# AY_Card_V2.net
KiCad netlist of a schematic drawn in EAGLE
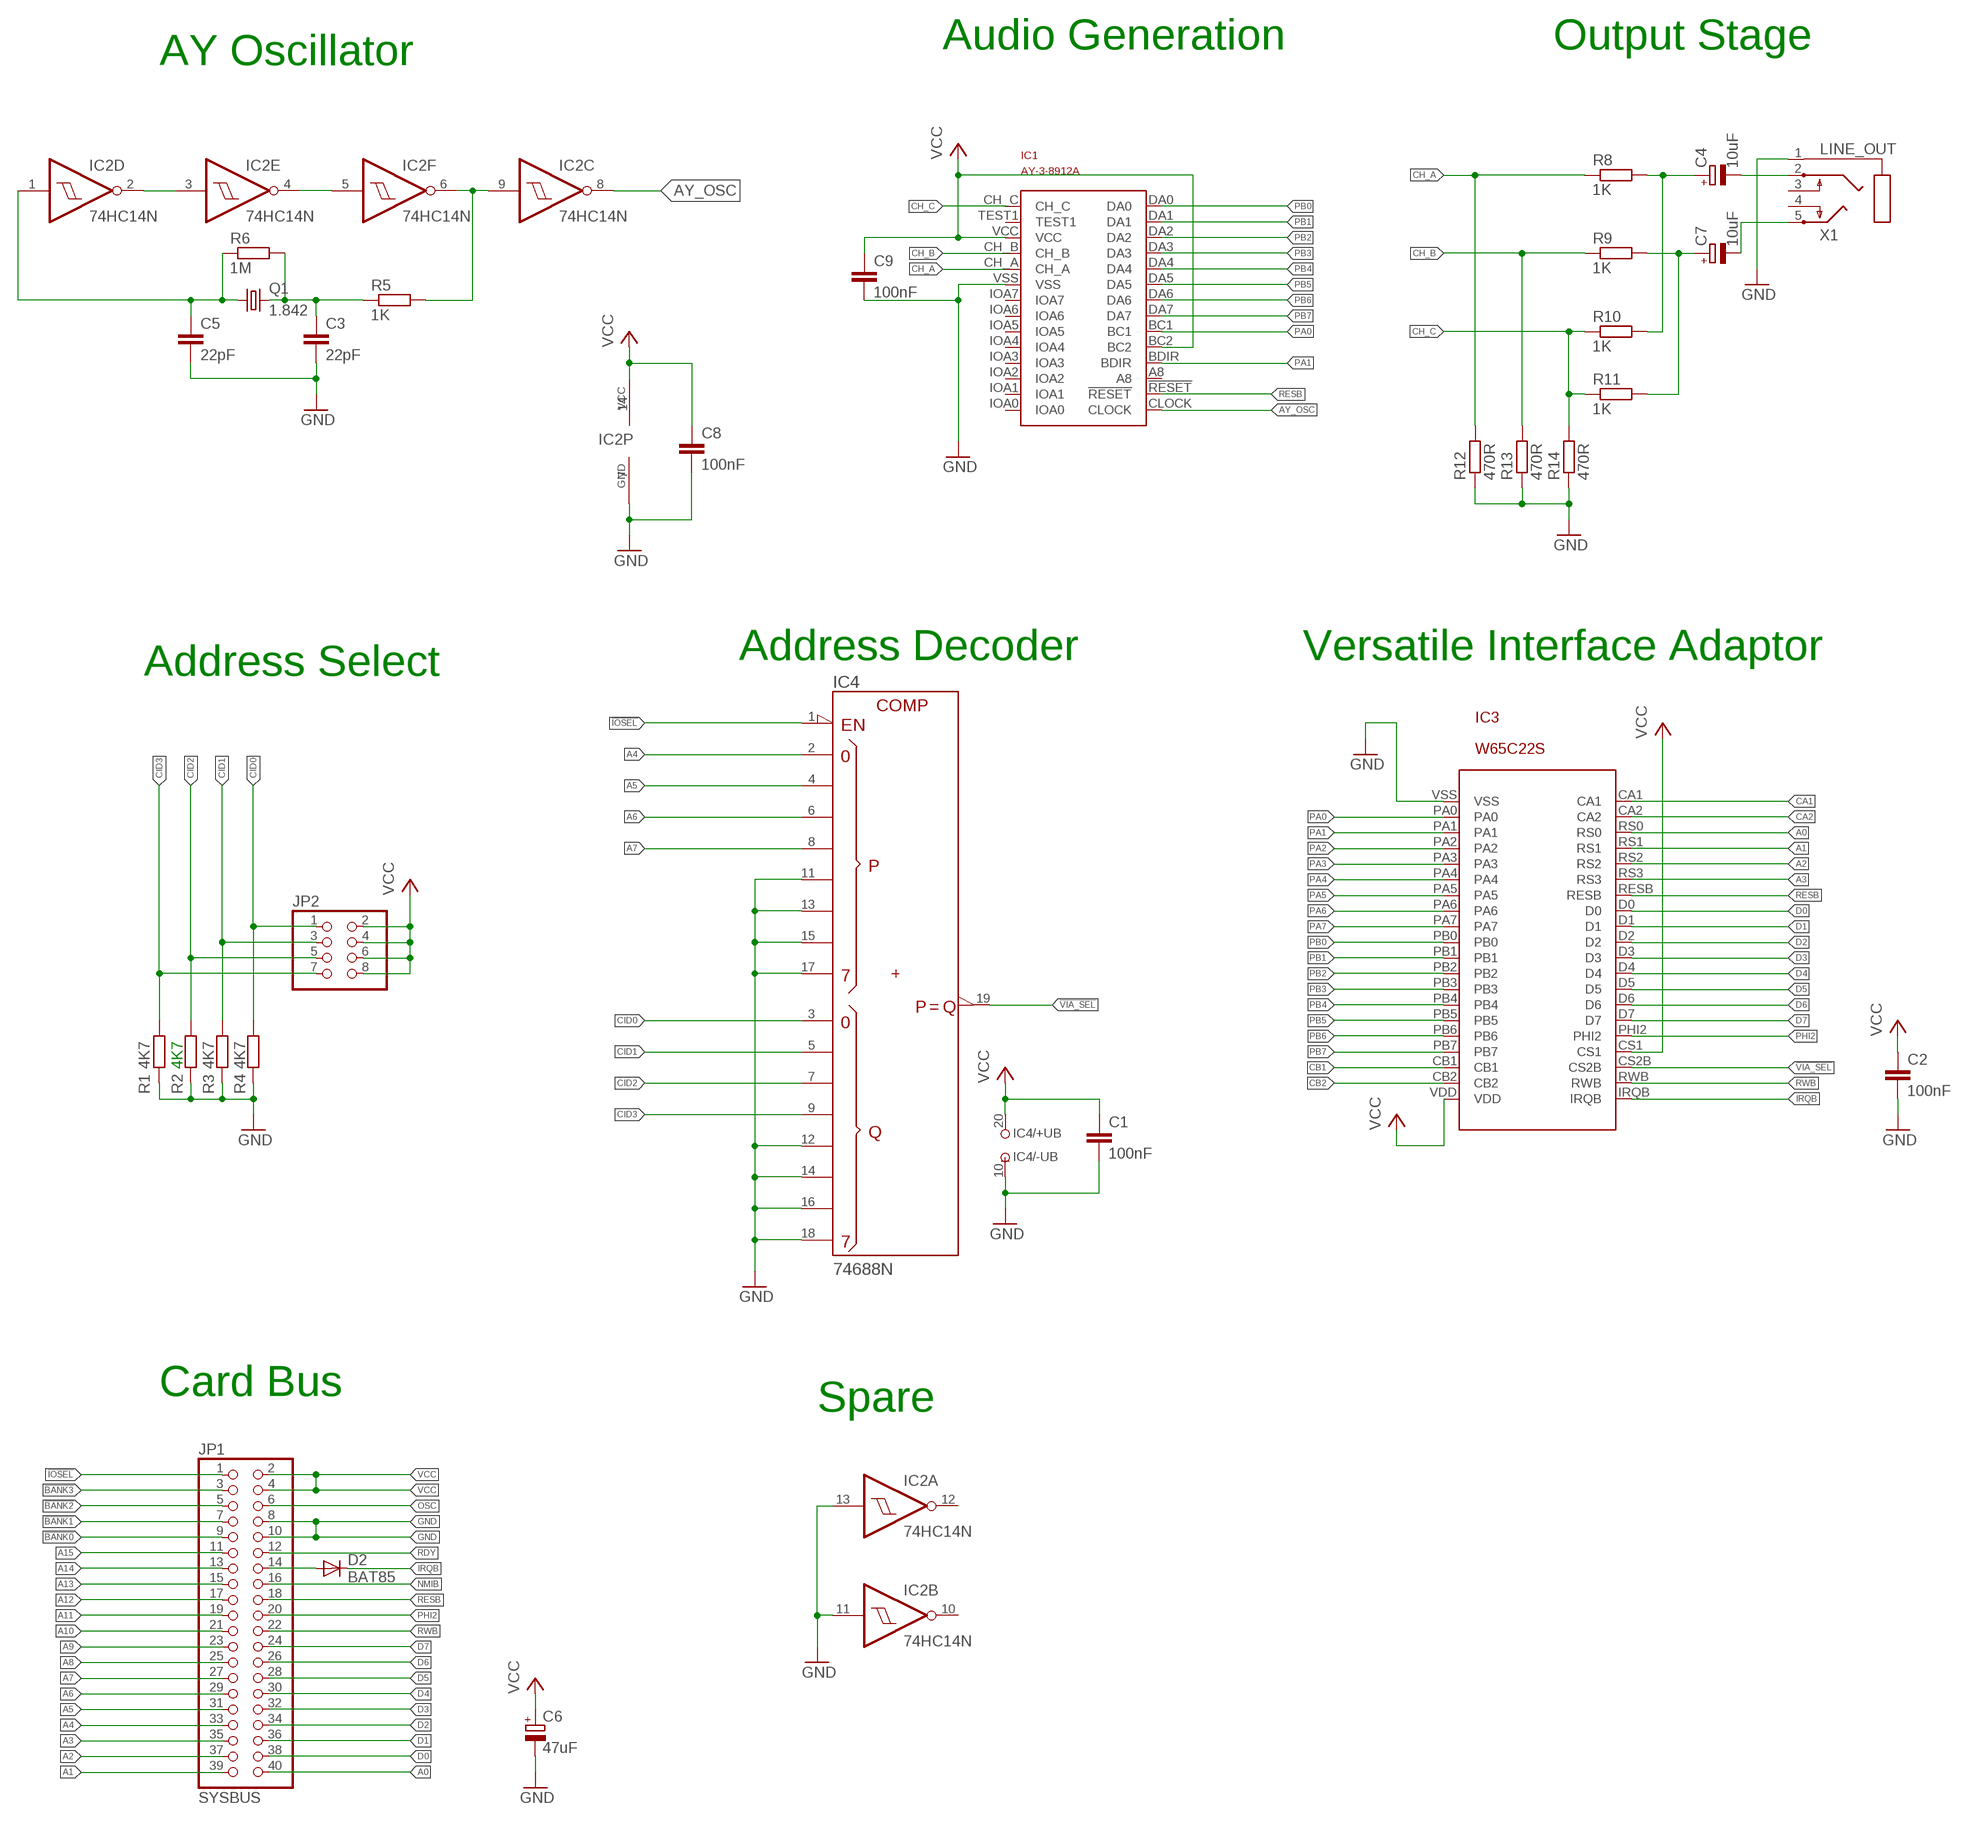
[diagram p0: schematic, sheet 1]

(export (version "E")
  (design (tool "Eeschema 10.0.6"))
  (components
    (comp (ref "C1")
      (value "100nF")
      (footprint "eagle-import:C050-025X075")
      (libsource (lib "eagle-import") (part "C-EU050-025X075"))
    )
    (comp (ref "C2")
      (value "100nF")
      (footprint "eagle-import:C050-025X075")
      (libsource (lib "eagle-import") (part "C-EU050-025X075"))
    )
    (comp (ref "C3")
      (value "22pF")
      (footprint "eagle-import:C050-025X075")
      (libsource (lib "eagle-import") (part "C-EU050-025X075"))
    )
    (comp (ref "C4")
      (value "10uF")
      (footprint "eagle-import:E2-5")
      (libsource (lib "eagle-import") (part "CPOL-EUE2-5"))
    )
    (comp (ref "C5")
      (value "22pF")
      (footprint "eagle-import:C050-025X075")
      (libsource (lib "eagle-import") (part "C-EU050-025X075"))
    )
    (comp (ref "C6")
      (value "47uF")
      (footprint "eagle-import:E2,5-7")
      (libsource (lib "eagle-import") (part "CPOL-EUE2.5-7"))
    )
    (comp (ref "C7")
      (value "10uF")
      (footprint "eagle-import:E2-5")
      (libsource (lib "eagle-import") (part "CPOL-EUE2-5"))
    )
    (comp (ref "C8")
      (value "100nF")
      (footprint "eagle-import:C050-025X075")
      (libsource (lib "eagle-import") (part "C-EU050-025X075"))
    )
    (comp (ref "C9")
      (value "100nF")
      (footprint "eagle-import:C050-025X075")
      (libsource (lib "eagle-import") (part "C-EU050-025X075"))
    )
    (comp (ref "D2")
      (value "BAT85")
      (footprint "eagle-import:DO34-7")
      (libsource (lib "eagle-import") (part "BAT81"))
    )
    (comp (ref "IC1")
      (value "AY-3-8912A")
      (footprint "eagle-import:DIP")
      (libsource (lib "eagle-import") (part "AY-3-8912-DIP"))
    )
    (comp (ref "IC2")
      (value "74HC14N")
      (footprint "eagle-import:DIL14")
      (libsource (lib "eagle-import") (part "7414N"))
    )
    (comp (ref "IC3")
      (value "W65C22S")
      (footprint "eagle-import:W65C22-DIP")
      (libsource (lib "eagle-import") (part "W65C22"))
    )
    (comp (ref "IC4")
      (value "74688N")
      (footprint "eagle-import:DIL20")
      (libsource (lib "eagle-import") (part "74688N"))
    )
    (comp (ref "JP1")
      (value "SYSBUS")
      (footprint "eagle-import:2X20_90")
      (libsource (lib "eagle-import") (part "PINHD-2X20/90"))
    )
    (comp (ref "JP2")
      (value "PINHD-2X4")
      (footprint "eagle-import:2X04")
      (libsource (lib "eagle-import") (part "PINHD-2X4"))
    )
    (comp (ref "Q1")
      (value "1.842")
      (footprint "eagle-import:HC49_S")
      (libsource (lib "eagle-import") (part "CRYSTALHC49S"))
    )
    (comp (ref "R1")
      (value "4K7")
      (footprint "eagle-import:0207_10")
      (libsource (lib "eagle-import") (part "R-EU_0207/10"))
    )
    (comp (ref "R2")
      (value "4K7")
      (footprint "eagle-import:0207_10")
      (libsource (lib "eagle-import") (part "R-EU_0207/10"))
    )
    (comp (ref "R3")
      (value "4K7")
      (footprint "eagle-import:0207_10")
      (libsource (lib "eagle-import") (part "R-EU_0207/10"))
    )
    (comp (ref "R4")
      (value "4K7")
      (footprint "eagle-import:0207_10")
      (libsource (lib "eagle-import") (part "R-EU_0207/10"))
    )
    (comp (ref "R5")
      (value "1K")
      (footprint "eagle-import:0207_2V")
      (libsource (lib "eagle-import") (part "R-EU_0207/2V"))
    )
    (comp (ref "R6")
      (value "1M")
      (footprint "eagle-import:0207_2V")
      (libsource (lib "eagle-import") (part "R-EU_0207/2V"))
    )
    (comp (ref "R8")
      (value "1K")
      (footprint "eagle-import:0207_2V")
      (libsource (lib "eagle-import") (part "R-EU_0207/2V"))
    )
    (comp (ref "R9")
      (value "1K")
      (footprint "eagle-import:0207_2V")
      (libsource (lib "eagle-import") (part "R-EU_0207/2V"))
    )
    (comp (ref "R10")
      (value "1K")
      (footprint "eagle-import:0207_2V")
      (libsource (lib "eagle-import") (part "R-EU_0207/2V"))
    )
    (comp (ref "R11")
      (value "1K")
      (footprint "eagle-import:0207_2V")
      (libsource (lib "eagle-import") (part "R-EU_0207/2V"))
    )
    (comp (ref "R12")
      (value "470R")
      (footprint "eagle-import:0207_2V")
      (libsource (lib "eagle-import") (part "R-EU_0207/2V"))
    )
    (comp (ref "R13")
      (value "470R")
      (footprint "eagle-import:0207_10")
      (libsource (lib "eagle-import") (part "R-EU_0207/10"))
    )
    (comp (ref "R14")
      (value "470R")
      (footprint "eagle-import:0207_10")
      (libsource (lib "eagle-import") (part "R-EU_0207/10"))
    )
    (comp (ref "X1")
      (value "LINE_OUT")
      (footprint "eagle-import:STX3100")
      (libsource (lib "eagle-import") (part "STEREOJACK"))
    )
  )
  (nets
    (net (code "1") (name "/~{BANK0}") (class "Default")
      (node (ref "JP1") (pin "9") (pinfunction "9_9") (pintype "passive"))
    )
    (net (code "2") (name "/~{BANK1}") (class "Default")
      (node (ref "JP1") (pin "7") (pinfunction "7_7") (pintype "passive"))
    )
    (net (code "3") (name "/~{BANK2}") (class "Default")
      (node (ref "JP1") (pin "5") (pinfunction "5_5") (pintype "passive"))
    )
    (net (code "4") (name "/~{BANK3}") (class "Default")
      (node (ref "JP1") (pin "3") (pinfunction "3_3") (pintype "passive"))
    )
    (net (code "5") (name "/~{IOSEL}") (class "Default")
      (node (ref "IC4") (pin "1") (pinfunction "~{G}_1") (pintype "input"))
      (node (ref "JP1") (pin "1") (pinfunction "1_1") (pintype "passive"))
    )
    (net (code "6") (name "/~{VIA_SEL}") (class "Default")
      (node (ref "IC3") (pin "CS2B") (pinfunction "CS2B_CS2B") (pintype "bidirectional"))
      (node (ref "IC4") (pin "19") (pinfunction "~{P=Q}_19") (pintype "output"))
    )
    (net (code "7") (name "A0") (class "Default")
      (node (ref "IC3") (pin "RS0") (pinfunction "RS0_RS0") (pintype "input"))
      (node (ref "JP1") (pin "40") (pinfunction "40_40") (pintype "passive"))
    )
    (net (code "8") (name "A1") (class "Default")
      (node (ref "IC3") (pin "RS1") (pinfunction "RS1_RS1") (pintype "input"))
      (node (ref "JP1") (pin "39") (pinfunction "39_39") (pintype "passive"))
    )
    (net (code "9") (name "A2") (class "Default")
      (node (ref "IC3") (pin "RS2") (pinfunction "RS2_RS2") (pintype "input"))
      (node (ref "JP1") (pin "37") (pinfunction "37_37") (pintype "passive"))
    )
    (net (code "10") (name "A3") (class "Default")
      (node (ref "IC3") (pin "RS3") (pinfunction "RS3_RS3") (pintype "input"))
      (node (ref "JP1") (pin "35") (pinfunction "35_35") (pintype "passive"))
    )
    (net (code "11") (name "A4") (class "Default")
      (node (ref "IC4") (pin "2") (pinfunction "P0_2") (pintype "input"))
      (node (ref "JP1") (pin "33") (pinfunction "33_33") (pintype "passive"))
    )
    (net (code "12") (name "A5") (class "Default")
      (node (ref "IC4") (pin "4") (pinfunction "P1_4") (pintype "input"))
      (node (ref "JP1") (pin "31") (pinfunction "31_31") (pintype "passive"))
    )
    (net (code "13") (name "A6") (class "Default")
      (node (ref "IC4") (pin "6") (pinfunction "P2_6") (pintype "input"))
      (node (ref "JP1") (pin "29") (pinfunction "29_29") (pintype "passive"))
    )
    (net (code "14") (name "A7") (class "Default")
      (node (ref "IC4") (pin "8") (pinfunction "P3_8") (pintype "input"))
      (node (ref "JP1") (pin "27") (pinfunction "27_27") (pintype "passive"))
    )
    (net (code "15") (name "A8") (class "Default")
      (node (ref "JP1") (pin "25") (pinfunction "25_25") (pintype "passive"))
    )
    (net (code "16") (name "A9") (class "Default")
      (node (ref "JP1") (pin "23") (pinfunction "23_23") (pintype "passive"))
    )
    (net (code "17") (name "A10") (class "Default")
      (node (ref "JP1") (pin "21") (pinfunction "21_21") (pintype "passive"))
    )
    (net (code "18") (name "A11") (class "Default")
      (node (ref "JP1") (pin "19") (pinfunction "19_19") (pintype "passive"))
    )
    (net (code "19") (name "A12") (class "Default")
      (node (ref "JP1") (pin "17") (pinfunction "17_17") (pintype "passive"))
    )
    (net (code "20") (name "A13") (class "Default")
      (node (ref "JP1") (pin "15") (pinfunction "15_15") (pintype "passive"))
    )
    (net (code "21") (name "A14") (class "Default")
      (node (ref "JP1") (pin "13") (pinfunction "13_13") (pintype "passive"))
    )
    (net (code "22") (name "A15") (class "Default")
      (node (ref "JP1") (pin "11") (pinfunction "11_11") (pintype "passive"))
    )
    (net (code "23") (name "AY_OSC") (class "Default")
      (node (ref "IC1") (pin "CLOCK") (pinfunction "CLOCK_CLOCK") (pintype "input"))
      (node (ref "IC2") (pin "8") (pinfunction "O_8") (pintype "output"))
    )
    (net (code "24") (name "CA1") (class "Default")
      (node (ref "IC3") (pin "CA1") (pinfunction "CA1_CA1") (pintype "bidirectional"))
    )
    (net (code "25") (name "CA2") (class "Default")
      (node (ref "IC3") (pin "CA2") (pinfunction "CA2_CA2") (pintype "bidirectional"))
    )
    (net (code "26") (name "CB1") (class "Default")
      (node (ref "IC3") (pin "CB1") (pinfunction "CB1_CB1") (pintype "bidirectional"))
    )
    (net (code "27") (name "CB2") (class "Default")
      (node (ref "IC3") (pin "CB2") (pinfunction "CB2_CB2") (pintype "bidirectional"))
    )
    (net (code "28") (name "CH_A") (class "Default")
      (node (ref "IC1") (pin "CH_A") (pinfunction "CH_A_CH_A") (pintype "output"))
      (node (ref "R12") (pin "2") (pinfunction "2_2") (pintype "passive"))
      (node (ref "R8") (pin "1") (pinfunction "1_1") (pintype "passive"))
    )
    (net (code "29") (name "CH_B") (class "Default")
      (node (ref "IC1") (pin "CH_B") (pinfunction "CH_B_CH_B") (pintype "output"))
      (node (ref "R13") (pin "2") (pinfunction "2_2") (pintype "passive"))
      (node (ref "R9") (pin "1") (pinfunction "1_1") (pintype "passive"))
    )
    (net (code "30") (name "CH_C") (class "Default")
      (node (ref "IC1") (pin "CH_C") (pinfunction "CH_C_CH_C") (pintype "output"))
      (node (ref "R10") (pin "1") (pinfunction "1_1") (pintype "passive"))
      (node (ref "R11") (pin "1") (pinfunction "1_1") (pintype "passive"))
      (node (ref "R14") (pin "2") (pinfunction "2_2") (pintype "passive"))
    )
    (net (code "31") (name "CID0") (class "Default")
      (node (ref "IC4") (pin "3") (pinfunction "Q0_3") (pintype "input"))
      (node (ref "JP2") (pin "1") (pinfunction "1_1") (pintype "passive"))
      (node (ref "R4") (pin "2") (pinfunction "2_2") (pintype "passive"))
    )
    (net (code "32") (name "CID1") (class "Default")
      (node (ref "IC4") (pin "5") (pinfunction "Q1_5") (pintype "input"))
      (node (ref "JP2") (pin "3") (pinfunction "3_3") (pintype "passive"))
      (node (ref "R3") (pin "2") (pinfunction "2_2") (pintype "passive"))
    )
    (net (code "33") (name "CID2") (class "Default")
      (node (ref "IC4") (pin "7") (pinfunction "Q2_7") (pintype "input"))
      (node (ref "JP2") (pin "5") (pinfunction "5_5") (pintype "passive"))
      (node (ref "R2") (pin "2") (pinfunction "2_2") (pintype "passive"))
    )
    (net (code "34") (name "CID3") (class "Default")
      (node (ref "IC4") (pin "9") (pinfunction "Q3_9") (pintype "input"))
      (node (ref "JP2") (pin "7") (pinfunction "7_7") (pintype "passive"))
      (node (ref "R1") (pin "2") (pinfunction "2_2") (pintype "passive"))
    )
    (net (code "35") (name "D0") (class "Default")
      (node (ref "IC3") (pin "D0") (pinfunction "D0_D0") (pintype "bidirectional"))
      (node (ref "JP1") (pin "38") (pinfunction "38_38") (pintype "passive"))
    )
    (net (code "36") (name "D1") (class "Default")
      (node (ref "IC3") (pin "D1") (pinfunction "D1_D1") (pintype "bidirectional"))
      (node (ref "JP1") (pin "36") (pinfunction "36_36") (pintype "passive"))
    )
    (net (code "37") (name "D2") (class "Default")
      (node (ref "IC3") (pin "D2") (pinfunction "D2_D2") (pintype "bidirectional"))
      (node (ref "JP1") (pin "34") (pinfunction "34_34") (pintype "passive"))
    )
    (net (code "38") (name "D3") (class "Default")
      (node (ref "IC3") (pin "D3") (pinfunction "D3_D3") (pintype "bidirectional"))
      (node (ref "JP1") (pin "32") (pinfunction "32_32") (pintype "passive"))
    )
    (net (code "39") (name "D4") (class "Default")
      (node (ref "IC3") (pin "D4") (pinfunction "D4_D4") (pintype "bidirectional"))
      (node (ref "JP1") (pin "30") (pinfunction "30_30") (pintype "passive"))
    )
    (net (code "40") (name "D5") (class "Default")
      (node (ref "IC3") (pin "D5") (pinfunction "D5_D5") (pintype "bidirectional"))
      (node (ref "JP1") (pin "28") (pinfunction "28_28") (pintype "passive"))
    )
    (net (code "41") (name "D6") (class "Default")
      (node (ref "IC3") (pin "D6") (pinfunction "D6_D6") (pintype "bidirectional"))
      (node (ref "JP1") (pin "26") (pinfunction "26_26") (pintype "passive"))
    )
    (net (code "42") (name "D7") (class "Default")
      (node (ref "IC3") (pin "D7") (pinfunction "D7_D7") (pintype "bidirectional"))
      (node (ref "JP1") (pin "24") (pinfunction "24_24") (pintype "passive"))
    )
    (net (code "43") (name "GND") (class "Default")
      (node (ref "C1") (pin "2") (pinfunction "2_2") (pintype "passive"))
      (node (ref "C2") (pin "2") (pinfunction "2_2") (pintype "passive"))
      (node (ref "C3") (pin "2") (pinfunction "2_2") (pintype "passive"))
      (node (ref "C5") (pin "2") (pinfunction "2_2") (pintype "passive"))
      (node (ref "C6") (pin "-") (pinfunction "-_-") (pintype "passive"))
      (node (ref "C8") (pin "2") (pinfunction "2_2") (pintype "passive"))
      (node (ref "C9") (pin "2") (pinfunction "2_2") (pintype "passive"))
      (node (ref "IC1") (pin "VSS") (pinfunction "VSS_VSS") (pintype "power_in"))
      (node (ref "IC2") (pin "11") (pinfunction "I_11") (pintype "input"))
      (node (ref "IC2") (pin "13") (pinfunction "I_13") (pintype "input"))
      (node (ref "IC2") (pin "7") (pinfunction "GND_7") (pintype "power_in"))
      (node (ref "IC3") (pin "VSS") (pinfunction "VSS_VSS") (pintype "power_in"))
      (node (ref "IC4") (pin "10") (pinfunction "-UB_10") (pintype "power_in"))
      (node (ref "IC4") (pin "11") (pinfunction "P4_11") (pintype "input"))
      (node (ref "IC4") (pin "12") (pinfunction "Q4_12") (pintype "input"))
      (node (ref "IC4") (pin "13") (pinfunction "P5_13") (pintype "input"))
      (node (ref "IC4") (pin "14") (pinfunction "Q5_14") (pintype "input"))
      (node (ref "IC4") (pin "15") (pinfunction "P6_15") (pintype "input"))
      (node (ref "IC4") (pin "16") (pinfunction "Q6_16") (pintype "input"))
      (node (ref "IC4") (pin "17") (pinfunction "P7_17") (pintype "input"))
      (node (ref "IC4") (pin "18") (pinfunction "Q7_18") (pintype "input"))
      (node (ref "JP1") (pin "10") (pinfunction "10_10") (pintype "passive"))
      (node (ref "JP1") (pin "8") (pinfunction "8_8") (pintype "passive"))
      (node (ref "R1") (pin "1") (pinfunction "1_1") (pintype "passive"))
      (node (ref "R12") (pin "1") (pinfunction "1_1") (pintype "passive"))
      (node (ref "R13") (pin "1") (pinfunction "1_1") (pintype "passive"))
      (node (ref "R14") (pin "1") (pinfunction "1_1") (pintype "passive"))
      (node (ref "R2") (pin "1") (pinfunction "1_1") (pintype "passive"))
      (node (ref "R3") (pin "1") (pinfunction "1_1") (pintype "passive"))
      (node (ref "R4") (pin "1") (pinfunction "1_1") (pintype "passive"))
      (node (ref "X1") (pin "1") (pinfunction "1_1") (pintype "passive"))
    )
    (net (code "44") (name "IRQB") (class "Default")
      (node (ref "D2") (pin "C") (pinfunction "C_C") (pintype "passive"))
      (node (ref "IC3") (pin "IRQB") (pinfunction "IRQB_IRQB") (pintype "output"))
    )
    (net (code "45") (name "NMIB") (class "Default")
      (node (ref "JP1") (pin "16") (pinfunction "16_16") (pintype "passive"))
    )
    (net (code "46") (name "Net-(C3-Pad1)") (class "Default")
      (node (ref "C3") (pin "1") (pinfunction "1_1") (pintype "passive"))
      (node (ref "Q1") (pin "2") (pinfunction "2_2") (pintype "passive"))
      (node (ref "R5") (pin "1") (pinfunction "1_1") (pintype "passive"))
      (node (ref "R6") (pin "2") (pinfunction "2_2") (pintype "passive"))
    )
    (net (code "47") (name "Net-(C4-Pad+)") (class "Default")
      (node (ref "C4") (pin "+") (pinfunction "+_+") (pintype "passive"))
      (node (ref "R10") (pin "2") (pinfunction "2_2") (pintype "passive"))
      (node (ref "R8") (pin "2") (pinfunction "2_2") (pintype "passive"))
    )
    (net (code "48") (name "Net-(C4-Pad-)") (class "Default")
      (node (ref "C4") (pin "-") (pinfunction "-_-") (pintype "passive"))
      (node (ref "X1") (pin "2") (pinfunction "2_2") (pintype "passive"))
    )
    (net (code "49") (name "Net-(C7-Pad+)") (class "Default")
      (node (ref "C7") (pin "+") (pinfunction "+_+") (pintype "passive"))
      (node (ref "R11") (pin "2") (pinfunction "2_2") (pintype "passive"))
      (node (ref "R9") (pin "2") (pinfunction "2_2") (pintype "passive"))
    )
    (net (code "50") (name "Net-(C7-Pad-)") (class "Default")
      (node (ref "C7") (pin "-") (pinfunction "-_-") (pintype "passive"))
      (node (ref "X1") (pin "5") (pinfunction "5_5") (pintype "passive"))
    )
    (net (code "51") (name "Net-(D2-PadA)") (class "Default")
      (node (ref "D2") (pin "A") (pinfunction "A_A") (pintype "passive"))
      (node (ref "JP1") (pin "14") (pinfunction "14_14") (pintype "passive"))
    )
    (net (code "52") (name "Net-(IC2C-I)") (class "Default")
      (node (ref "IC2") (pin "6") (pinfunction "O_6") (pintype "output"))
      (node (ref "IC2") (pin "9") (pinfunction "I_9") (pintype "input"))
      (node (ref "R5") (pin "2") (pinfunction "2_2") (pintype "passive"))
    )
    (net (code "53") (name "Net-(IC2D-I)") (class "Default")
      (node (ref "C5") (pin "1") (pinfunction "1_1") (pintype "passive"))
      (node (ref "IC2") (pin "1") (pinfunction "I_1") (pintype "input"))
      (node (ref "Q1") (pin "1") (pinfunction "1_1") (pintype "passive"))
      (node (ref "R6") (pin "1") (pinfunction "1_1") (pintype "passive"))
    )
    (net (code "54") (name "Net-(IC2D-O)") (class "Default")
      (node (ref "IC2") (pin "2") (pinfunction "O_2") (pintype "output"))
      (node (ref "IC2") (pin "3") (pinfunction "I_3") (pintype "input"))
    )
    (net (code "55") (name "Net-(IC2E-O)") (class "Default")
      (node (ref "IC2") (pin "4") (pinfunction "O_4") (pintype "output"))
      (node (ref "IC2") (pin "5") (pinfunction "I_5") (pintype "input"))
    )
    (net (code "56") (name "OSC") (class "Default")
      (node (ref "JP1") (pin "6") (pinfunction "6_6") (pintype "passive"))
    )
    (net (code "57") (name "PA0") (class "Default")
      (node (ref "IC1") (pin "BC1") (pinfunction "BC1_BC1") (pintype "input"))
      (node (ref "IC3") (pin "PA0") (pinfunction "PA0_PA0") (pintype "bidirectional"))
    )
    (net (code "58") (name "PA1") (class "Default")
      (node (ref "IC1") (pin "BDIR") (pinfunction "BDIR_BDIR") (pintype "input"))
      (node (ref "IC3") (pin "PA1") (pinfunction "PA1_PA1") (pintype "bidirectional"))
    )
    (net (code "59") (name "PA2") (class "Default")
      (node (ref "IC3") (pin "PA2") (pinfunction "PA2_PA2") (pintype "bidirectional"))
    )
    (net (code "60") (name "PA3") (class "Default")
      (node (ref "IC3") (pin "PA3") (pinfunction "PA3_PA3") (pintype "bidirectional"))
    )
    (net (code "61") (name "PA4") (class "Default")
      (node (ref "IC3") (pin "PA4") (pinfunction "PA4_PA4") (pintype "bidirectional"))
    )
    (net (code "62") (name "PA5") (class "Default")
      (node (ref "IC3") (pin "PA5") (pinfunction "PA5_PA5") (pintype "bidirectional"))
    )
    (net (code "63") (name "PA6") (class "Default")
      (node (ref "IC3") (pin "PA6") (pinfunction "PA6_PA6") (pintype "bidirectional"))
    )
    (net (code "64") (name "PA7") (class "Default")
      (node (ref "IC3") (pin "PA7") (pinfunction "PA7_PA7") (pintype "bidirectional"))
    )
    (net (code "65") (name "PB0") (class "Default")
      (node (ref "IC1") (pin "DA0") (pinfunction "DA0_DA0") (pintype "bidirectional"))
      (node (ref "IC3") (pin "PB0") (pinfunction "PB0_PB0") (pintype "bidirectional"))
    )
    (net (code "66") (name "PB1") (class "Default")
      (node (ref "IC1") (pin "DA1") (pinfunction "DA1_DA1") (pintype "bidirectional"))
      (node (ref "IC3") (pin "PB1") (pinfunction "PB1_PB1") (pintype "bidirectional"))
    )
    (net (code "67") (name "PB2") (class "Default")
      (node (ref "IC1") (pin "DA2") (pinfunction "DA2_DA2") (pintype "bidirectional"))
      (node (ref "IC3") (pin "PB2") (pinfunction "PB2_PB2") (pintype "bidirectional"))
    )
    (net (code "68") (name "PB3") (class "Default")
      (node (ref "IC1") (pin "DA3") (pinfunction "DA3_DA3") (pintype "bidirectional"))
      (node (ref "IC3") (pin "PB3") (pinfunction "PB3_PB3") (pintype "bidirectional"))
    )
    (net (code "69") (name "PB4") (class "Default")
      (node (ref "IC1") (pin "DA4") (pinfunction "DA4_DA4") (pintype "bidirectional"))
      (node (ref "IC3") (pin "PB4") (pinfunction "PB4_PB4") (pintype "bidirectional"))
    )
    (net (code "70") (name "PB5") (class "Default")
      (node (ref "IC1") (pin "DA5") (pinfunction "DA5_DA5") (pintype "bidirectional"))
      (node (ref "IC3") (pin "PB5") (pinfunction "PB5_PB5") (pintype "bidirectional"))
    )
    (net (code "71") (name "PB6") (class "Default")
      (node (ref "IC1") (pin "DA6") (pinfunction "DA6_DA6") (pintype "bidirectional"))
      (node (ref "IC3") (pin "PB6") (pinfunction "PB6_PB6") (pintype "bidirectional"))
    )
    (net (code "72") (name "PB7") (class "Default")
      (node (ref "IC1") (pin "DA7") (pinfunction "DA7_DA7") (pintype "bidirectional"))
      (node (ref "IC3") (pin "PB7") (pinfunction "PB7_PB7") (pintype "bidirectional"))
    )
    (net (code "73") (name "PHI2") (class "Default")
      (node (ref "IC3") (pin "PHI2") (pinfunction "PHI2_PHI2") (pintype "input"))
      (node (ref "JP1") (pin "20") (pinfunction "20_20") (pintype "passive"))
    )
    (net (code "74") (name "RDY") (class "Default")
      (node (ref "JP1") (pin "12") (pinfunction "12_12") (pintype "passive"))
    )
    (net (code "75") (name "RESB") (class "Default")
      (node (ref "IC1") (pin "!RESET") (pinfunction "~{RESET}_!RESET") (pintype "input"))
      (node (ref "IC3") (pin "RESB") (pinfunction "RESB_RESB") (pintype "input"))
      (node (ref "JP1") (pin "18") (pinfunction "18_18") (pintype "passive"))
    )
    (net (code "76") (name "RWB") (class "Default")
      (node (ref "IC3") (pin "RWB") (pinfunction "RWB_RWB") (pintype "input"))
      (node (ref "JP1") (pin "22") (pinfunction "22_22") (pintype "passive"))
    )
    (net (code "77") (name "VCC") (class "Default")
      (node (ref "C1") (pin "1") (pinfunction "1_1") (pintype "passive"))
      (node (ref "C2") (pin "1") (pinfunction "1_1") (pintype "passive"))
      (node (ref "C6") (pin "+") (pinfunction "+_+") (pintype "passive"))
      (node (ref "C8") (pin "1") (pinfunction "1_1") (pintype "passive"))
      (node (ref "C9") (pin "1") (pinfunction "1_1") (pintype "passive"))
      (node (ref "IC1") (pin "BC2") (pinfunction "BC2_BC2") (pintype "input"))
      (node (ref "IC1") (pin "VCC") (pinfunction "VCC_VCC") (pintype "power_in"))
      (node (ref "IC2") (pin "14") (pinfunction "VCC_14") (pintype "power_in"))
      (node (ref "IC3") (pin "CS1") (pinfunction "CS1_CS1") (pintype "bidirectional"))
      (node (ref "IC3") (pin "VDD") (pinfunction "VDD_VDD") (pintype "power_in"))
      (node (ref "IC4") (pin "20") (pinfunction "+UB_20") (pintype "power_in"))
      (node (ref "JP1") (pin "2") (pinfunction "2_2") (pintype "passive"))
      (node (ref "JP1") (pin "4") (pinfunction "4_4") (pintype "passive"))
      (node (ref "JP2") (pin "2") (pinfunction "2_2") (pintype "passive"))
      (node (ref "JP2") (pin "4") (pinfunction "4_4") (pintype "passive"))
      (node (ref "JP2") (pin "6") (pinfunction "6_6") (pintype "passive"))
      (node (ref "JP2") (pin "8") (pinfunction "8_8") (pintype "passive"))
    )
    (net (code "78") (name "unconnected-(IC1-PadA8)") (class "Default")
      (node (ref "IC1") (pin "A8") (pinfunction "A8_A8") (pintype "input"))
    )
    (net (code "79") (name "unconnected-(IC1-PadIOA0)") (class "Default")
      (node (ref "IC1") (pin "IOA0") (pinfunction "IOA0_IOA0") (pintype "bidirectional"))
    )
    (net (code "80") (name "unconnected-(IC1-PadIOA1)") (class "Default")
      (node (ref "IC1") (pin "IOA1") (pinfunction "IOA1_IOA1") (pintype "bidirectional"))
    )
    (net (code "81") (name "unconnected-(IC1-PadIOA2)") (class "Default")
      (node (ref "IC1") (pin "IOA2") (pinfunction "IOA2_IOA2") (pintype "bidirectional"))
    )
    (net (code "82") (name "unconnected-(IC1-PadIOA3)") (class "Default")
      (node (ref "IC1") (pin "IOA3") (pinfunction "IOA3_IOA3") (pintype "bidirectional"))
    )
    (net (code "83") (name "unconnected-(IC1-PadIOA4)") (class "Default")
      (node (ref "IC1") (pin "IOA4") (pinfunction "IOA4_IOA4") (pintype "bidirectional"))
    )
    (net (code "84") (name "unconnected-(IC1-PadIOA5)") (class "Default")
      (node (ref "IC1") (pin "IOA5") (pinfunction "IOA5_IOA5") (pintype "bidirectional"))
    )
    (net (code "85") (name "unconnected-(IC1-PadIOA6)") (class "Default")
      (node (ref "IC1") (pin "IOA6") (pinfunction "IOA6_IOA6") (pintype "bidirectional"))
    )
    (net (code "86") (name "unconnected-(IC1-PadIOA7)") (class "Default")
      (node (ref "IC1") (pin "IOA7") (pinfunction "IOA7_IOA7") (pintype "bidirectional"))
    )
    (net (code "87") (name "unconnected-(IC1-PadTEST1)") (class "Default")
      (node (ref "IC1") (pin "TEST1") (pinfunction "TEST1_TEST1") (pintype "no_connect"))
    )
    (net (code "88") (name "unconnected-(IC2A-O-Pad12)") (class "Default")
      (node (ref "IC2") (pin "12") (pinfunction "O_12") (pintype "output"))
    )
    (net (code "89") (name "unconnected-(IC2B-O-Pad10)") (class "Default")
      (node (ref "IC2") (pin "10") (pinfunction "O_10") (pintype "output"))
    )
    (net (code "90") (name "unconnected-(X1-Pad3)") (class "Default")
      (node (ref "X1") (pin "3") (pinfunction "3_3") (pintype "passive"))
    )
    (net (code "91") (name "unconnected-(X1-Pad4)") (class "Default")
      (node (ref "X1") (pin "4") (pinfunction "4_4") (pintype "passive"))
    )
  )
)
